# bt_441.net
KiCad netlist of a schematic drawn in EAGLE
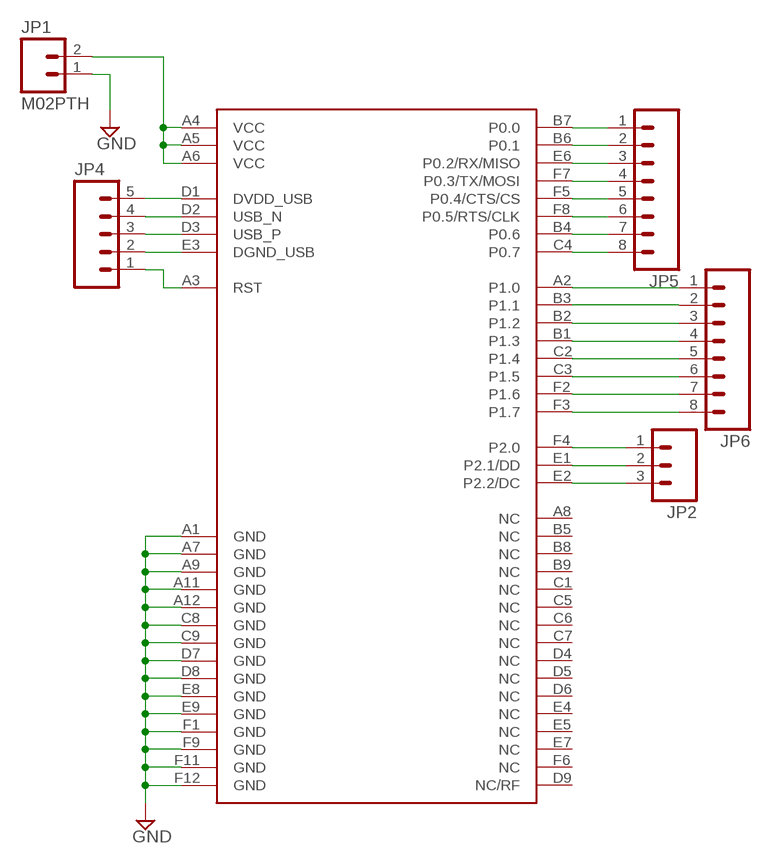
[diagram p0: schematic, sheet 1]

(export (version "E")
  (design (tool "Eeschema 10.0.6"))
  (components
    (comp (ref "JP1")
      (value "M02PTH")
      (footprint "eagle-import:1X02")
      (libsource (lib "eagle-import") (part "M02PTH"))
    )
    (comp (ref "JP2")
      (value "M03PTH")
      (footprint "eagle-import:1X03")
      (libsource (lib "eagle-import") (part "M03PTH"))
    )
    (comp (ref "JP4")
      (value "M05PTH")
      (footprint "eagle-import:1X05")
      (libsource (lib "eagle-import") (part "M05PTH"))
    )
    (comp (ref "JP5")
      (value "M081X08")
      (footprint "eagle-import:1X08")
      (libsource (lib "eagle-import") (part "M081X08"))
    )
    (comp (ref "JP6")
      (value "M081X08")
      (footprint "eagle-import:1X08")
      (libsource (lib "eagle-import") (part "M081X08"))
    )
    (comp (ref "U$1")
      (value "PAN1720")
      (footprint "eagle-import:PAN1720")
      (libsource (lib "eagle-import") (part "PAN1720"))
    )
  )
  (nets
    (net (code "1") (name "GND") (class "Default")
      (node (ref "JP1") (pin "1") (pinfunction "1_1") (pintype "passive"))
      (node (ref "U$1") (pin "A1") (pinfunction "GND_A1") (pintype "bidirectional"))
      (node (ref "U$1") (pin "A11") (pinfunction "GND_A11") (pintype "bidirectional"))
      (node (ref "U$1") (pin "A12") (pinfunction "GND_A12") (pintype "bidirectional"))
      (node (ref "U$1") (pin "A7") (pinfunction "GND_A7") (pintype "bidirectional"))
      (node (ref "U$1") (pin "A9") (pinfunction "GND_A9") (pintype "bidirectional"))
      (node (ref "U$1") (pin "C8") (pinfunction "GND_C8") (pintype "bidirectional"))
      (node (ref "U$1") (pin "C9") (pinfunction "GND_C9") (pintype "bidirectional"))
      (node (ref "U$1") (pin "D7") (pinfunction "GND_D7") (pintype "bidirectional"))
      (node (ref "U$1") (pin "D8") (pinfunction "GND_D8") (pintype "bidirectional"))
      (node (ref "U$1") (pin "E8") (pinfunction "GND_E8") (pintype "bidirectional"))
      (node (ref "U$1") (pin "E9") (pinfunction "GND_E9") (pintype "bidirectional"))
      (node (ref "U$1") (pin "F1") (pinfunction "GND_F1") (pintype "bidirectional"))
      (node (ref "U$1") (pin "F11") (pinfunction "GND_F11") (pintype "bidirectional"))
      (node (ref "U$1") (pin "F12") (pinfunction "GND_F12") (pintype "bidirectional"))
      (node (ref "U$1") (pin "F9") (pinfunction "GND_F9") (pintype "bidirectional"))
    )
    (net (code "2") (name "Net-(JP1-Pad2)") (class "Default")
      (node (ref "JP1") (pin "2") (pinfunction "2_2") (pintype "passive"))
      (node (ref "U$1") (pin "A4") (pinfunction "VCC_A4") (pintype "bidirectional"))
      (node (ref "U$1") (pin "A5") (pinfunction "VCC_A5") (pintype "bidirectional"))
      (node (ref "U$1") (pin "A6") (pinfunction "VCC_A6") (pintype "bidirectional"))
    )
    (net (code "3") (name "Net-(U$1-DGND_USB)") (class "Default")
      (node (ref "JP4") (pin "2") (pinfunction "2_2") (pintype "passive"))
      (node (ref "U$1") (pin "E3") (pinfunction "DGND_USB_E3") (pintype "bidirectional"))
    )
    (net (code "4") (name "Net-(U$1-DVDD_USB)") (class "Default")
      (node (ref "JP4") (pin "5") (pinfunction "5_5") (pintype "passive"))
      (node (ref "U$1") (pin "D1") (pinfunction "DVDD_USB_D1") (pintype "bidirectional"))
    )
    (net (code "5") (name "Net-(U$1-P0.0)") (class "Default")
      (node (ref "JP5") (pin "1") (pinfunction "1_1") (pintype "passive"))
      (node (ref "U$1") (pin "B7") (pinfunction "P0.0_B7") (pintype "bidirectional"))
    )
    (net (code "6") (name "Net-(U$1-P0.1)") (class "Default")
      (node (ref "JP5") (pin "2") (pinfunction "2_2") (pintype "passive"))
      (node (ref "U$1") (pin "B6") (pinfunction "P0.1_B6") (pintype "bidirectional"))
    )
    (net (code "7") (name "Net-(U$1-P0.2{slash}RX{slash}MISO)") (class "Default")
      (node (ref "JP5") (pin "3") (pinfunction "3_3") (pintype "passive"))
      (node (ref "U$1") (pin "E6") (pinfunction "P0.2/RX/MISO_E6") (pintype "bidirectional"))
    )
    (net (code "8") (name "Net-(U$1-P0.3{slash}TX{slash}MOSI)") (class "Default")
      (node (ref "JP5") (pin "4") (pinfunction "4_4") (pintype "passive"))
      (node (ref "U$1") (pin "F7") (pinfunction "P0.3/TX/MOSI_F7") (pintype "bidirectional"))
    )
    (net (code "9") (name "Net-(U$1-P0.4{slash}CTS{slash}CS)") (class "Default")
      (node (ref "JP5") (pin "5") (pinfunction "5_5") (pintype "passive"))
      (node (ref "U$1") (pin "F5") (pinfunction "P0.4/CTS/CS_F5") (pintype "bidirectional"))
    )
    (net (code "10") (name "Net-(U$1-P0.5{slash}RTS{slash}CLK)") (class "Default")
      (node (ref "JP5") (pin "6") (pinfunction "6_6") (pintype "passive"))
      (node (ref "U$1") (pin "F8") (pinfunction "P0.5/RTS/CLK_F8") (pintype "bidirectional"))
    )
    (net (code "11") (name "Net-(U$1-P0.6)") (class "Default")
      (node (ref "JP5") (pin "7") (pinfunction "7_7") (pintype "passive"))
      (node (ref "U$1") (pin "B4") (pinfunction "P0.6_B4") (pintype "bidirectional"))
    )
    (net (code "12") (name "Net-(U$1-P0.7)") (class "Default")
      (node (ref "JP5") (pin "8") (pinfunction "8_8") (pintype "passive"))
      (node (ref "U$1") (pin "C4") (pinfunction "P0.7_C4") (pintype "bidirectional"))
    )
    (net (code "13") (name "Net-(U$1-P1.0)") (class "Default")
      (node (ref "JP6") (pin "1") (pinfunction "1_1") (pintype "passive"))
      (node (ref "U$1") (pin "A2") (pinfunction "P1.0_A2") (pintype "bidirectional"))
    )
    (net (code "14") (name "Net-(U$1-P1.1)") (class "Default")
      (node (ref "JP6") (pin "2") (pinfunction "2_2") (pintype "passive"))
      (node (ref "U$1") (pin "B3") (pinfunction "P1.1_B3") (pintype "bidirectional"))
    )
    (net (code "15") (name "Net-(U$1-P1.2)") (class "Default")
      (node (ref "JP6") (pin "3") (pinfunction "3_3") (pintype "passive"))
      (node (ref "U$1") (pin "B2") (pinfunction "P1.2_B2") (pintype "bidirectional"))
    )
    (net (code "16") (name "Net-(U$1-P1.3)") (class "Default")
      (node (ref "JP6") (pin "4") (pinfunction "4_4") (pintype "passive"))
      (node (ref "U$1") (pin "B1") (pinfunction "P1.3_B1") (pintype "bidirectional"))
    )
    (net (code "17") (name "Net-(U$1-P1.4)") (class "Default")
      (node (ref "JP6") (pin "5") (pinfunction "5_5") (pintype "passive"))
      (node (ref "U$1") (pin "C2") (pinfunction "P1.4_C2") (pintype "bidirectional"))
    )
    (net (code "18") (name "Net-(U$1-P1.5)") (class "Default")
      (node (ref "JP6") (pin "6") (pinfunction "6_6") (pintype "passive"))
      (node (ref "U$1") (pin "C3") (pinfunction "P1.5_C3") (pintype "bidirectional"))
    )
    (net (code "19") (name "Net-(U$1-P1.6)") (class "Default")
      (node (ref "JP6") (pin "7") (pinfunction "7_7") (pintype "passive"))
      (node (ref "U$1") (pin "F2") (pinfunction "P1.6_F2") (pintype "bidirectional"))
    )
    (net (code "20") (name "Net-(U$1-P1.7)") (class "Default")
      (node (ref "JP6") (pin "8") (pinfunction "8_8") (pintype "passive"))
      (node (ref "U$1") (pin "F3") (pinfunction "P1.7_F3") (pintype "bidirectional"))
    )
    (net (code "21") (name "Net-(U$1-P2.0)") (class "Default")
      (node (ref "JP2") (pin "1") (pinfunction "1_1") (pintype "passive"))
      (node (ref "U$1") (pin "F4") (pinfunction "P2.0_F4") (pintype "bidirectional"))
    )
    (net (code "22") (name "Net-(U$1-P2.1{slash}DD)") (class "Default")
      (node (ref "JP2") (pin "2") (pinfunction "2_2") (pintype "passive"))
      (node (ref "U$1") (pin "E1") (pinfunction "P2.1/DD_E1") (pintype "bidirectional"))
    )
    (net (code "23") (name "Net-(U$1-P2.2{slash}DC)") (class "Default")
      (node (ref "JP2") (pin "3") (pinfunction "3_3") (pintype "passive"))
      (node (ref "U$1") (pin "E2") (pinfunction "P2.2/DC_E2") (pintype "bidirectional"))
    )
    (net (code "24") (name "Net-(U$1-RST)") (class "Default")
      (node (ref "JP4") (pin "1") (pinfunction "1_1") (pintype "passive"))
      (node (ref "U$1") (pin "A3") (pinfunction "RST_A3") (pintype "bidirectional"))
    )
    (net (code "25") (name "Net-(U$1-USB_N)") (class "Default")
      (node (ref "JP4") (pin "4") (pinfunction "4_4") (pintype "passive"))
      (node (ref "U$1") (pin "D2") (pinfunction "USB_N_D2") (pintype "bidirectional"))
    )
    (net (code "26") (name "Net-(U$1-USB_P)") (class "Default")
      (node (ref "JP4") (pin "3") (pinfunction "3_3") (pintype "passive"))
      (node (ref "U$1") (pin "D3") (pinfunction "USB_P_D3") (pintype "bidirectional"))
    )
    (net (code "27") (name "unconnected-(U$1-NC-PadA8)") (class "Default")
      (node (ref "U$1") (pin "A8") (pinfunction "NC_A8") (pintype "bidirectional"))
    )
    (net (code "28") (name "unconnected-(U$1-NC-PadB5)") (class "Default")
      (node (ref "U$1") (pin "B5") (pinfunction "NC_B5") (pintype "bidirectional"))
    )
    (net (code "29") (name "unconnected-(U$1-NC-PadB8)") (class "Default")
      (node (ref "U$1") (pin "B8") (pinfunction "NC_B8") (pintype "bidirectional"))
    )
    (net (code "30") (name "unconnected-(U$1-NC-PadB9)") (class "Default")
      (node (ref "U$1") (pin "B9") (pinfunction "NC_B9") (pintype "bidirectional"))
    )
    (net (code "31") (name "unconnected-(U$1-NC-PadC1)") (class "Default")
      (node (ref "U$1") (pin "C1") (pinfunction "NC_C1") (pintype "bidirectional"))
    )
    (net (code "32") (name "unconnected-(U$1-NC-PadC5)") (class "Default")
      (node (ref "U$1") (pin "C5") (pinfunction "NC_C5") (pintype "bidirectional"))
    )
    (net (code "33") (name "unconnected-(U$1-NC-PadC6)") (class "Default")
      (node (ref "U$1") (pin "C6") (pinfunction "NC_C6") (pintype "bidirectional"))
    )
    (net (code "34") (name "unconnected-(U$1-NC-PadC7)") (class "Default")
      (node (ref "U$1") (pin "C7") (pinfunction "NC_C7") (pintype "bidirectional"))
    )
    (net (code "35") (name "unconnected-(U$1-NC-PadD4)") (class "Default")
      (node (ref "U$1") (pin "D4") (pinfunction "NC_D4") (pintype "bidirectional"))
    )
    (net (code "36") (name "unconnected-(U$1-NC-PadD5)") (class "Default")
      (node (ref "U$1") (pin "D5") (pinfunction "NC_D5") (pintype "bidirectional"))
    )
    (net (code "37") (name "unconnected-(U$1-NC-PadD6)") (class "Default")
      (node (ref "U$1") (pin "D6") (pinfunction "NC_D6") (pintype "bidirectional"))
    )
    (net (code "38") (name "unconnected-(U$1-NC-PadE4)") (class "Default")
      (node (ref "U$1") (pin "E4") (pinfunction "NC_E4") (pintype "bidirectional"))
    )
    (net (code "39") (name "unconnected-(U$1-NC-PadE5)") (class "Default")
      (node (ref "U$1") (pin "E5") (pinfunction "NC_E5") (pintype "bidirectional"))
    )
    (net (code "40") (name "unconnected-(U$1-NC-PadE7)") (class "Default")
      (node (ref "U$1") (pin "E7") (pinfunction "NC_E7") (pintype "bidirectional"))
    )
    (net (code "41") (name "unconnected-(U$1-NC-PadF6)") (class "Default")
      (node (ref "U$1") (pin "F6") (pinfunction "NC_F6") (pintype "bidirectional"))
    )
    (net (code "42") (name "unconnected-(U$1-NC{slash}RF-PadD9)") (class "Default")
      (node (ref "U$1") (pin "D9") (pinfunction "NC/RF_D9") (pintype "bidirectional"))
    )
  )
)
